# RS485_Rain_Sensor_Socket.net
KiCad netlist of a schematic drawn in Altium Designer
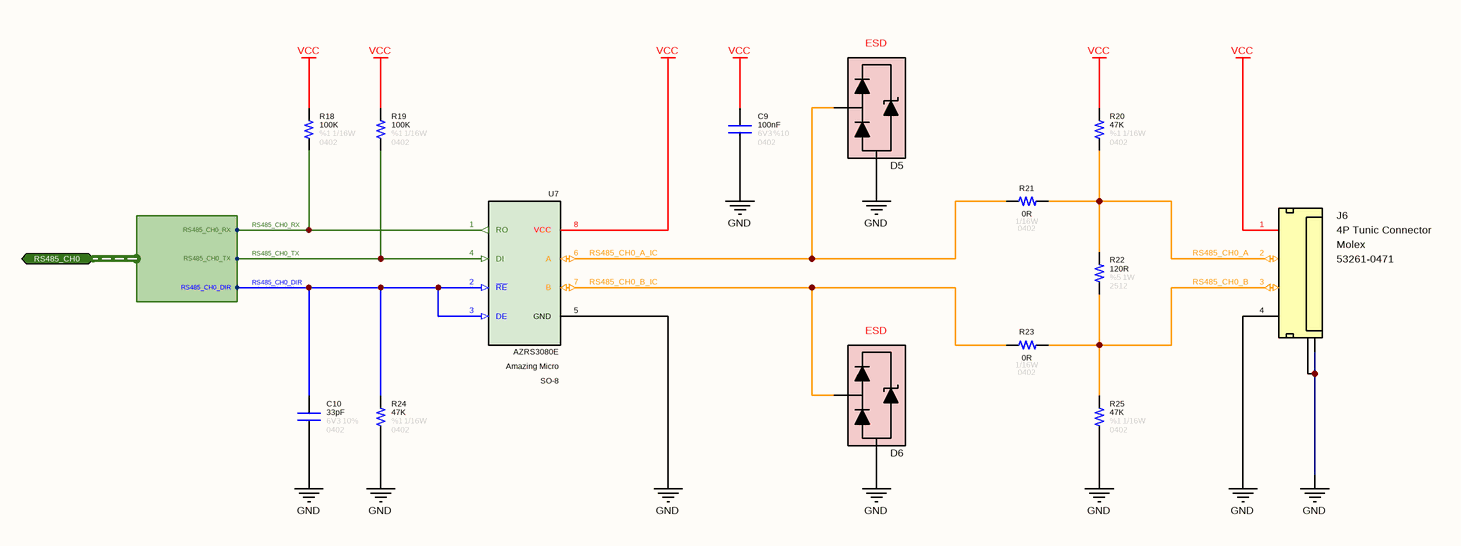
[diagram p0: RS485 Rain Sensor Socket.SchDoc]

(export (version "E")
  (design (tool "Eeschema 10.0.6"))
  (components
    (comp (ref "C9")
      (value "100nF")
      (footprint "CAPACITOR_0402")
      (description "Capacitor - 100nF [0402-6V3] (Ceramic)")
      (fields
        (field (name "MANUFACTURER PART NUMBER") "04026D104KAT4A")
        (field (name "TOLERANCE") "%10")
        (field (name "VOLTAGE") "6V3")
        (field (name "CASE") "0402")
        (field (name "Comment") "Capacitor - 100nF [0402] (Ceramic)")
      )
      (libsource (lib "P101DA_Library") (part "Capacitor - 100nF [0402-6V3]"))
    )
    (comp (ref "C10")
      (value "33pF")
      (footprint "CAPACITOR_0402")
      (description "Capacitor - 33pF [0402] (Ceramic)")
      (fields
        (field (name "MANUFACTURER PART NUMBER") "C0402C330J9RACAUTO")
        (field (name "TOLERANCE") "10%")
        (field (name "CASE") "0402")
        (field (name "VOLTAGE") "6V3")
      )
      (libsource (lib "P101DA_Library") (part "Capacitor - 33pF [0402-6V3]"))
    )
    (comp (ref "D5")
      (value "0402ESDA-MLP1")
      (footprint "ESD_0402")
      (description "SUPPRESSOR ESD 30VDC 0402 HFREE")
      (libsource (lib "P101DA_Library") (part "Diode - TPD1E05U06DPYR"))
    )
    (comp (ref "D6")
      (value "0402ESDA-MLP1")
      (footprint "ESD_0402")
      (description "SUPPRESSOR ESD 30VDC 0402 HFREE")
      (libsource (lib "P101DA_Library") (part "Diode - TPD1E05U06DPYR"))
    )
    (comp (ref "J6")
      (value "4P SMD Tunic Connector")
      (footprint "Connector_Tunic 4P")
      (description "Mini Tunic Connector with 4P")
      (fields
        (field (name "MANUFACTURER NAME") "Molex")
        (field (name "MANUFACTURER PART NUMBER") "53261-0471")
      )
      (libsource (lib "P101DA_Library") (part "Connector - Mini Tunic 4P (1.25)"))
    )
    (comp (ref "R18")
      (value "100K")
      (footprint "RESISTOR_0402")
      (description "Thick Film Resistors - SMD 1/16 W 100 KOhm 1%")
      (fields
        (field (name "MANUFACTURER PART NUMBER") "CRCW0402100KFKED")
        (field (name "TOLERANCE") "%1")
        (field (name "CASE") "0402")
        (field (name "POWER") "1/16W")
        (field (name "Comment") "100K - 0402 - %1 - 1/16W")
      )
      (libsource (lib "P101DA_Library") (part "Resistor - 100K [0402]"))
    )
    (comp (ref "R19")
      (value "100K")
      (footprint "RESISTOR_0402")
      (description "Thick Film Resistors - SMD 1/16 W 100 KOhm 1%")
      (fields
        (field (name "MANUFACTURER PART NUMBER") "CRCW0402100KFKED")
        (field (name "TOLERANCE") "%1")
        (field (name "CASE") "0402")
        (field (name "POWER") "1/16W")
        (field (name "Comment") "100K - 0402 - %1 - 1/16W")
      )
      (libsource (lib "P101DA_Library") (part "Resistor - 100K [0402]"))
    )
    (comp (ref "R20")
      (value "47K")
      (footprint "RESISTOR_0402")
      (description "Thick Film Resistors - SMD 1/16 W 47 KOhm 1%")
      (fields
        (field (name "MANUFACTURER PART NUMBER") "CRCW040247K0FKED")
        (field (name "TOLERANCE") "%1")
        (field (name "CASE") "0402")
        (field (name "POWER") "1/16W")
        (field (name "Comment") "47K - 0402 - %1 - 1/16W")
      )
      (libsource (lib "P101DA_Library") (part "Resistor - 47K [0402]"))
    )
    (comp (ref "R21")
      (value "0R")
      (footprint "RESISTOR_0402")
      (description "Thick Film Resistors - SMD 1/16 W 0 Ohm")
      (fields
        (field (name "MANUFACTURER PART NUMBER") "CRCW04020000Z0ED")
        (field (name "CASE") "0402")
        (field (name "POWER") "1/16W")
        (field (name "Comment") "0R - 0402 - %1 - 1/16W")
      )
      (libsource (lib "P101DA_Library") (part "Resistor - 0R [0402]"))
    )
    (comp (ref "R22")
      (value "120R")
      (footprint "RESISTOR_2512")
      (description "Thick Film Resistors - SMD 1 W 120 Ohm 5%")
      (fields
        (field (name "MANUFACTURER PART NUMBER") "RC2512JK-07120RL")
        (field (name "TOLERANCE") "%5")
        (field (name "CASE") "2512")
        (field (name "POWER") "1W")
        (field (name "Comment") "120R - 2512 - %5 - 1W")
      )
      (libsource (lib "P101DA_Library") (part "Resistor - 120R [2512]"))
    )
    (comp (ref "R23")
      (value "0R")
      (footprint "RESISTOR_0402")
      (description "Thick Film Resistors - SMD 1/16 W 0 Ohm")
      (fields
        (field (name "MANUFACTURER PART NUMBER") "CRCW04020000Z0ED")
        (field (name "CASE") "0402")
        (field (name "POWER") "1/16W")
        (field (name "Comment") "0R - 0402 - %1 - 1/16W")
      )
      (libsource (lib "P101DA_Library") (part "Resistor - 0R [0402]"))
    )
    (comp (ref "R24")
      (value "47K")
      (footprint "RESISTOR_0402")
      (description "Thick Film Resistors - SMD 1/16 W 47 KOhm 1%")
      (fields
        (field (name "MANUFACTURER PART NUMBER") "CRCW040247K0FKED")
        (field (name "TOLERANCE") "%1")
        (field (name "CASE") "0402")
        (field (name "POWER") "1/16W")
        (field (name "Comment") "47K - 0402 - %1 - 1/16W")
      )
      (libsource (lib "P101DA_Library") (part "Resistor - 47K [0402]"))
    )
    (comp (ref "R25")
      (value "47K")
      (footprint "RESISTOR_0402")
      (description "Thick Film Resistors - SMD 1/16 W 47 KOhm 1%")
      (fields
        (field (name "MANUFACTURER PART NUMBER") "CRCW040247K0FKED")
        (field (name "TOLERANCE") "%1")
        (field (name "CASE") "0402")
        (field (name "POWER") "1/16W")
        (field (name "Comment") "47K - 0402 - %1 - 1/16W")
      )
      (libsource (lib "P101DA_Library") (part "Resistor - 47K [0402]"))
    )
    (comp (ref "U7")
      (value "RS485 Modulator")
      (footprint "SOP-8L (AZRS3080E)")
      (description "Half-duplex RS485 transceiver.")
      (fields
        (field (name "CASE") "SO-8")
        (field (name "MANUFACTURER PART NUMBER") "AZRS3080E")
        (field (name "MANUFACTURER NAME") "Amazing Micro")
      )
      (libsource (lib "P101DA_Library") (part "IC - AZRS3080E"))
    )
  )
  (nets
    (net (code "2") (name "/RS485_CH0_A") (class "Default")
      (node (ref "J6") (pin "2") (pinfunction "Pin-2_2") (pintype "bidirectional"))
      (node (ref "R20") (pin "1") (pinfunction "1_1") (pintype "passive"))
      (node (ref "R21") (pin "1") (pinfunction "1_1") (pintype "passive"))
      (node (ref "R22") (pin "2") (pinfunction "2_2") (pintype "passive"))
    )
    (net (code "3") (name "/RS485_CH0_A_IC") (class "Default")
      (node (ref "D5") (pin "1") (pinfunction "I/O_1") (pintype "passive"))
      (node (ref "R21") (pin "2") (pinfunction "2_2") (pintype "passive"))
      (node (ref "U7") (pin "6") (pinfunction "A_6") (pintype "bidirectional"))
    )
    (net (code "4") (name "/RS485_CH0_B") (class "Default")
      (node (ref "J6") (pin "3") (pinfunction "Pin-3_3") (pintype "bidirectional"))
      (node (ref "R22") (pin "1") (pinfunction "1_1") (pintype "passive"))
      (node (ref "R23") (pin "1") (pinfunction "1_1") (pintype "passive"))
      (node (ref "R25") (pin "2") (pinfunction "2_2") (pintype "passive"))
    )
    (net (code "5") (name "/RS485_CH0_B_IC") (class "Default")
      (node (ref "D6") (pin "1") (pinfunction "I/O_1") (pintype "passive"))
      (node (ref "R23") (pin "2") (pinfunction "2_2") (pintype "passive"))
      (node (ref "U7") (pin "7") (pinfunction "B_7") (pintype "bidirectional"))
    )
    (net (code "6") (name "/RS485_CH0_DIR") (class "Default")
      (node (ref "C10") (pin "2") (pinfunction "2_2") (pintype "passive"))
      (node (ref "R24") (pin "2") (pinfunction "2_2") (pintype "passive"))
      (node (ref "U7") (pin "2") (pinfunction "~{RE}_2") (pintype "input"))
      (node (ref "U7") (pin "3") (pinfunction "DE_3") (pintype "input"))
    )
    (net (code "7") (name "/RS485_CH0_RX") (class "Default")
      (node (ref "R18") (pin "1") (pinfunction "1_1") (pintype "passive"))
      (node (ref "U7") (pin "1") (pinfunction "RO_1") (pintype "output"))
    )
    (net (code "8") (name "/RS485_CH0_TX") (class "Default")
      (node (ref "R19") (pin "1") (pinfunction "1_1") (pintype "passive"))
      (node (ref "U7") (pin "4") (pinfunction "DI_4") (pintype "input"))
    )
    (net (code "10") (name "GND") (class "Default")
      (node (ref "C10") (pin "1") (pinfunction "1_1") (pintype "passive"))
      (node (ref "C9") (pin "1") (pinfunction "1_1") (pintype "passive"))
      (node (ref "D5") (pin "2") (pinfunction "GND_2") (pintype "passive"))
      (node (ref "D6") (pin "2") (pinfunction "GND_2") (pintype "passive"))
      (node (ref "J6") (pin "4") (pinfunction "Pin-4_4") (pintype "power_in"))
      (node (ref "J6") (pin "5") (pinfunction "GND_5") (pintype "passive"))
      (node (ref "J6") (pin "6") (pinfunction "GND_6") (pintype "passive"))
      (node (ref "R24") (pin "1") (pinfunction "1_1") (pintype "passive"))
      (node (ref "R25") (pin "1") (pinfunction "1_1") (pintype "passive"))
      (node (ref "U7") (pin "5") (pinfunction "GND_5") (pintype "passive"))
    )
    (net (code "11") (name "VCC") (class "Default")
      (node (ref "C9") (pin "2") (pinfunction "2_2") (pintype "passive"))
      (node (ref "J6") (pin "1") (pinfunction "Pin-1_1") (pintype "power_in"))
      (node (ref "R18") (pin "2") (pinfunction "2_2") (pintype "passive"))
      (node (ref "R19") (pin "2") (pinfunction "2_2") (pintype "passive"))
      (node (ref "R20") (pin "2") (pinfunction "2_2") (pintype "passive"))
      (node (ref "U7") (pin "8") (pinfunction "VCC_8") (pintype "power_in"))
    )
  )
)
